# Step-Down_Converter.net
KiCad netlist of a schematic drawn in Altium Designer
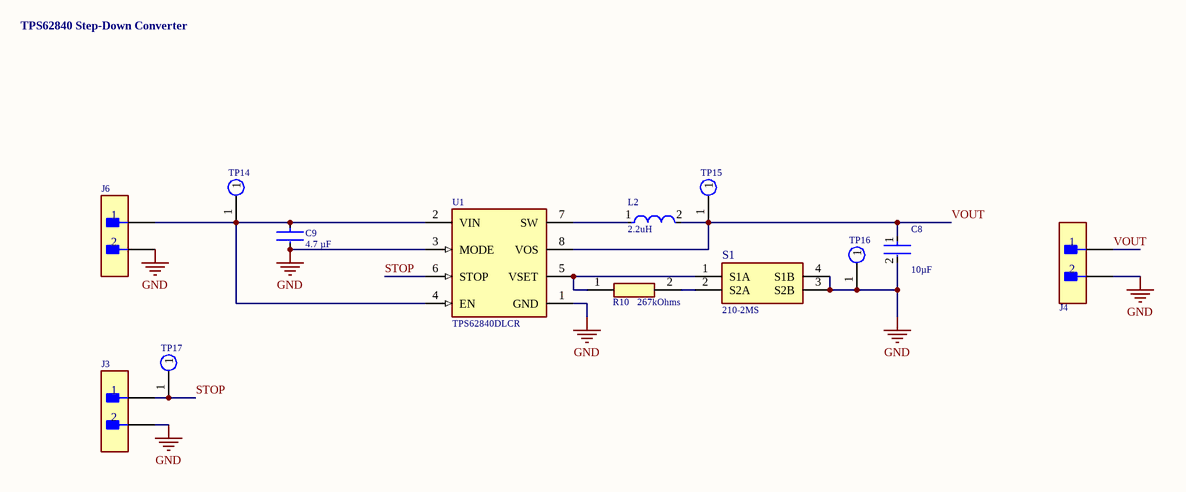
[diagram p0: Step-Down Converter.SchDoc]

(export (version "E")
  (design (tool "Eeschema 10.0.6"))
  (components
    (comp (ref "C8")
      (value "10µF")
      (footprint "FP-GRM21B-0_1-MFG")
      (fields (field (name "TOLERANCE") "10%") (field (name "VOLTAGE") "16V"))
      (libsource (lib "Altium Content Vault") (part "b4654b650e69147ec39a6b967a45e02"))
    )
    (comp (ref "C9")
      (value "4.7 µF")
      (footprint "FP-CC0603-DA-MFG")
      (description "CAP CER 4.7UF 10V X5R 0603 CC0603KRX5R6BB475")
      (fields (field (name "MANUFACTURER PART NUMBER") "CC0603KRX5R6BB475") (field (name "VOLTAGE") "10 V"))
      (libsource (lib "Altium Content Vault") (part "11868f565c42a9108669ba33697ecf6"))
    )
    (comp (ref "J3")
      (value "B2B-XH-A(LF)(SN)")
      (footprint "FP-B2B-XH-A_LF_SN-MFG")
      (description "CONN HEADER VERT 2POS 2.5MM")
      (libsource (lib "Altium Content Vault") (part "3bc925449376181038e59eaffc5286c"))
    )
    (comp (ref "J4")
      (value "B2B-XH-A(LF)(SN)")
      (footprint "FP-B2B-XH-A_LF_SN-MFG")
      (description "CONN HEADER VERT 2POS 2.5MM")
      (libsource (lib "Altium Content Vault") (part "3bc925449376181038e59eaffc5286c"))
    )
    (comp (ref "J6")
      (value "B2B-XH-A(LF)(SN)")
      (footprint "FP-B2B-XH-A_LF_SN-MFG")
      (description "CONN HEADER VERT 2POS 2.5MM")
      (libsource (lib "Altium Content Vault") (part "3bc925449376181038e59eaffc5286c"))
    )
    (comp (ref "L2")
      (value "2.2uH")
      (footprint "FP-NR3015-MFG")
      (description "SMD Power Inductors 2.2uH ±20% 1.48A 72mΩ NR3015T2R2M")
      (fields (field (name "TOLERANCE") "20%"))
      (libsource (lib "Altium Content Vault") (part "725321dda6339637d4d059423bc1c3c"))
    )
    (comp (ref "R10")
      (value "267kOhms")
      (footprint "SamacSys:RESC1608X55N")
      (description "Resistor")
      (fields (field (name "MANUFACTURER_PART_NUMBER") "RC0603FR-07267KL"))
      (libsource (lib "*") (part "RC0603FR-07267KL"))
    )
    (comp (ref "S1")
      (value "210-2MS")
      (footprint "SamacSys:DIP775W63P254L655H458Q4N")
      (description "Switch")
      (fields (field (name "MOUSER PART NUMBER") "774-2102MS"))
      (libsource (lib "*") (part "210-2MS"))
    )
    (comp (ref "TP14")
      (value "S2761-46R")
      (footprint "SamacSys:S276146R")
      (description "Test Point")
      (fields (field (name "MOUSER PART NUMBER") "855-S2761-46R"))
      (libsource (lib "SamacSys") (part "S2761-46R"))
    )
    (comp (ref "TP15")
      (value "S2761-46R")
      (footprint "SamacSys:S276146R")
      (description "Test Point")
      (fields (field (name "MOUSER PART NUMBER") "855-S2761-46R"))
      (libsource (lib "SamacSys") (part "S2761-46R"))
    )
    (comp (ref "TP16")
      (value "S2761-46R")
      (footprint "SamacSys:S276146R")
      (description "Test Point")
      (fields (field (name "MOUSER PART NUMBER") "855-S2761-46R"))
      (libsource (lib "SamacSys") (part "S2761-46R"))
    )
    (comp (ref "TP17")
      (value "S2761-46R")
      (footprint "SamacSys:S276146R")
      (description "Test Point")
      (fields (field (name "MOUSER PART NUMBER") "855-S2761-46R"))
      (libsource (lib "SamacSys") (part "S2761-46R"))
    )
    (comp (ref "U1")
      (value "TPS62840DLCR")
      (footprint "FP-DLC0008B-MFG")
      (description "ULTRA LOW IQ BUCK CONVERTER")
      (fields
        (field (name "OCTOPART") "https://octopart.com/tps62840dlcr-texas+instruments-103121111")
        (field (name "MANUFACTURER") "Texas Instruments")
      )
      (libsource (lib "Altium Content Vault") (part "09bc3a9b1d58a1376198d6b923e8c7c"))
    )
  )
  (nets
    (net (code "1") (name "/STOP") (class "Default")
      (node (ref "J3") (pin "1") (pinfunction "1_1") (pintype "passive"))
      (node (ref "TP17") (pin "1") (pinfunction "1_1") (pintype "passive"))
      (node (ref "U1") (pin "6") (pinfunction "STOP_6") (pintype "input"))
    )
    (net (code "2") (name "/VOUT") (class "Default")
      (node (ref "C8") (pin "1") (pinfunction "1_1") (pintype "passive"))
      (node (ref "J4") (pin "1") (pinfunction "1_1") (pintype "passive"))
      (node (ref "L2") (pin "2") (pinfunction "2_2") (pintype "passive"))
      (node (ref "TP15") (pin "1") (pinfunction "1_1") (pintype "passive"))
      (node (ref "U1") (pin "8") (pinfunction "VOS_8") (pintype "passive"))
    )
    (net (code "3") (name "GND") (class "Default")
      (node (ref "C8") (pin "2") (pinfunction "2_2") (pintype "passive"))
      (node (ref "C9") (pin "2") (pinfunction "2_2") (pintype "passive"))
      (node (ref "J3") (pin "2") (pinfunction "2_2") (pintype "passive"))
      (node (ref "J4") (pin "2") (pinfunction "2_2") (pintype "passive"))
      (node (ref "J6") (pin "2") (pinfunction "2_2") (pintype "passive"))
      (node (ref "S1") (pin "3") (pinfunction "S2B_3") (pintype "passive"))
      (node (ref "S1") (pin "4") (pinfunction "S1B_4") (pintype "passive"))
      (node (ref "TP16") (pin "1") (pinfunction "1_1") (pintype "passive"))
      (node (ref "U1") (pin "1") (pinfunction "GND_1") (pintype "power_in"))
      (node (ref "U1") (pin "3") (pinfunction "MODE_3") (pintype "input"))
    )
    (net (code "4") (name "Net-(S1-S1A)") (class "Default")
      (node (ref "R10") (pin "1") (pinfunction "1_1") (pintype "passive"))
      (node (ref "S1") (pin "1") (pinfunction "S1A_1") (pintype "passive"))
      (node (ref "U1") (pin "5") (pinfunction "VSET_5") (pintype "passive"))
    )
    (net (code "5") (name "Net-(S1-S2A)") (class "Default")
      (node (ref "R10") (pin "2") (pinfunction "2_2") (pintype "passive"))
      (node (ref "S1") (pin "2") (pinfunction "S2A_2") (pintype "passive"))
    )
    (net (code "6") (name "Net-(U1-EN)") (class "Default")
      (node (ref "C9") (pin "1") (pinfunction "1_1") (pintype "passive"))
      (node (ref "J6") (pin "1") (pinfunction "1_1") (pintype "passive"))
      (node (ref "TP14") (pin "1") (pinfunction "1_1") (pintype "passive"))
      (node (ref "U1") (pin "2") (pinfunction "VIN_2") (pintype "power_in"))
      (node (ref "U1") (pin "4") (pinfunction "EN_4") (pintype "input"))
    )
    (net (code "7") (name "Net-(U1-SW)") (class "Default")
      (node (ref "L2") (pin "1") (pinfunction "1_1") (pintype "passive"))
      (node (ref "U1") (pin "7") (pinfunction "SW_7") (pintype "passive"))
    )
  )
)
